# qec_pcb_v2.net
KiCad netlist of a schematic drawn in EAGLE
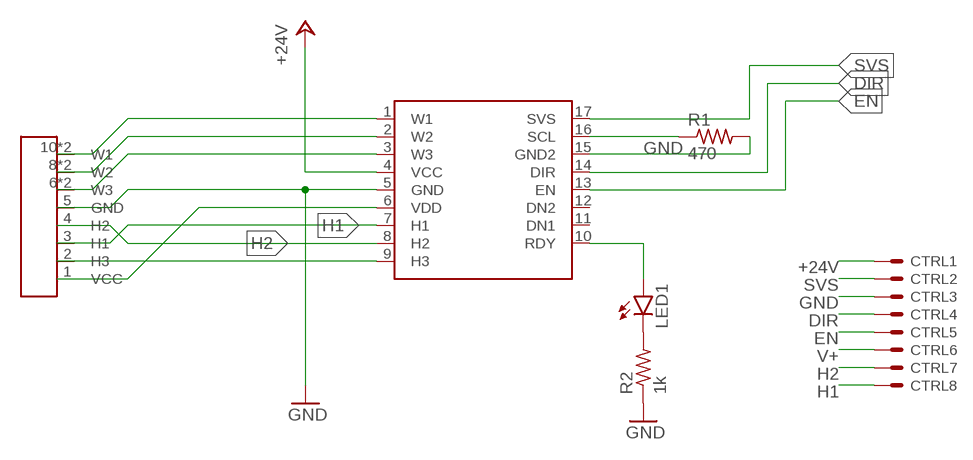
[diagram p0: schematic, sheet 1]

(export (version "E")
  (design (tool "Eeschema 10.0.6"))
  (components
    (comp (ref "CTRL")
      (value "JST8")
      (footprint "eagle-import:JST")
      (libsource (lib "eagle-import") (part "JST8"))
    )
    (comp (ref "K1")
      (value "68611114122")
      (footprint "eagle-import:68611114122")
      (libsource (lib "eagle-import") (part "68611114122"))
    )
    (comp (ref "LED1")
      (value "LEDCHIPLED_0805")
      (footprint "eagle-import:CHIPLED_0805")
      (libsource (lib "eagle-import") (part "LEDCHIPLED_0805"))
    )
    (comp (ref "R1")
      (value "470")
      (footprint "eagle-import:M0805")
      (libsource (lib "eagle-import") (part "R-US_M0805"))
    )
    (comp (ref "R2")
      (value "1k")
      (footprint "eagle-import:M0805")
      (libsource (lib "eagle-import") (part "R-US_M0805"))
    )
    (comp (ref "U$1")
      (value "1-Q-EC1-Q-EC-SMD")
      (footprint "eagle-import:1-Q-EC-SMD")
      (libsource (lib "eagle-import") (part "1-Q-EC1-Q-EC-SMD"))
    )
  )
  (nets
    (net (code "1") (name "+24V") (class "Default")
      (node (ref "CTRL") (pin "1") (pinfunction "S_1") (pintype "passive"))
      (node (ref "U$1") (pin "4") (pinfunction "VCC_4") (pintype "bidirectional"))
    )
    (net (code "2") (name "/V+") (class "Default")
      (node (ref "CTRL") (pin "6") (pinfunction "S_6") (pintype "passive"))
      (node (ref "K1") (pin "1") (pinfunction "VCC_1") (pintype "bidirectional"))
      (node (ref "U$1") (pin "6") (pinfunction "VDD_6") (pintype "bidirectional"))
    )
    (net (code "3") (name "DIR") (class "Default")
      (node (ref "CTRL") (pin "4") (pinfunction "S_4") (pintype "passive"))
      (node (ref "U$1") (pin "14") (pinfunction "DIR_14") (pintype "bidirectional"))
    )
    (net (code "4") (name "EN") (class "Default")
      (node (ref "CTRL") (pin "5") (pinfunction "S_5") (pintype "passive"))
      (node (ref "U$1") (pin "13") (pinfunction "EN_13") (pintype "bidirectional"))
    )
    (net (code "5") (name "GND") (class "Default")
      (node (ref "CTRL") (pin "3") (pinfunction "S_3") (pintype "passive"))
      (node (ref "K1") (pin "5") (pinfunction "GND_5") (pintype "bidirectional"))
      (node (ref "R1") (pin "2") (pinfunction "2_2") (pintype "passive"))
      (node (ref "R2") (pin "1") (pinfunction "1_1") (pintype "passive"))
      (node (ref "U$1") (pin "15") (pinfunction "GND2_15") (pintype "bidirectional"))
      (node (ref "U$1") (pin "5") (pinfunction "GND_5") (pintype "bidirectional"))
    )
    (net (code "6") (name "H1") (class "Default")
      (node (ref "CTRL") (pin "8") (pinfunction "S_8") (pintype "passive"))
      (node (ref "K1") (pin "3") (pinfunction "H1_3") (pintype "bidirectional"))
      (node (ref "U$1") (pin "7") (pinfunction "H1_7") (pintype "bidirectional"))
    )
    (net (code "7") (name "H2") (class "Default")
      (node (ref "CTRL") (pin "7") (pinfunction "S_7") (pintype "passive"))
      (node (ref "K1") (pin "4") (pinfunction "H2_4") (pintype "bidirectional"))
      (node (ref "U$1") (pin "8") (pinfunction "H2_8") (pintype "bidirectional"))
    )
    (net (code "8") (name "Net-(K1-H3)") (class "Default")
      (node (ref "K1") (pin "2") (pinfunction "H3_2") (pintype "bidirectional"))
      (node (ref "U$1") (pin "9") (pinfunction "H3_9") (pintype "bidirectional"))
    )
    (net (code "9") (name "Net-(LED1-PadC)") (class "Default")
      (node (ref "LED1") (pin "C") (pinfunction "C_C") (pintype "passive"))
      (node (ref "R2") (pin "2") (pinfunction "2_2") (pintype "passive"))
    )
    (net (code "10") (name "Net-(U$1-RDY)") (class "Default")
      (node (ref "LED1") (pin "A") (pinfunction "A_A") (pintype "passive"))
      (node (ref "U$1") (pin "10") (pinfunction "RDY_10") (pintype "bidirectional"))
    )
    (net (code "11") (name "Net-(U$1-SCL)") (class "Default")
      (node (ref "R1") (pin "1") (pinfunction "1_1") (pintype "passive"))
      (node (ref "U$1") (pin "16") (pinfunction "SCL_16") (pintype "bidirectional"))
    )
    (net (code "12") (name "Net-(U$1-W1)") (class "Default")
      (node (ref "K1") (pin "10") (pinfunction "W1_10") (pintype "bidirectional"))
      (node (ref "K1") (pin "11") (pinfunction "W1_11") (pintype "bidirectional"))
      (node (ref "U$1") (pin "1") (pinfunction "W1_1") (pintype "bidirectional"))
    )
    (net (code "13") (name "Net-(U$1-W2)") (class "Default")
      (node (ref "K1") (pin "8") (pinfunction "W2_8") (pintype "bidirectional"))
      (node (ref "K1") (pin "9") (pinfunction "W2_9") (pintype "bidirectional"))
      (node (ref "U$1") (pin "2") (pinfunction "W2_2") (pintype "bidirectional"))
    )
    (net (code "14") (name "Net-(U$1-W3)") (class "Default")
      (node (ref "K1") (pin "6") (pinfunction "W3_6") (pintype "bidirectional"))
      (node (ref "K1") (pin "7") (pinfunction "W3_7") (pintype "bidirectional"))
      (node (ref "U$1") (pin "3") (pinfunction "W3_3") (pintype "bidirectional"))
    )
    (net (code "15") (name "SVS") (class "Default")
      (node (ref "CTRL") (pin "2") (pinfunction "S_2") (pintype "passive"))
      (node (ref "U$1") (pin "17") (pinfunction "SVS_17") (pintype "bidirectional"))
    )
    (net (code "16") (name "unconnected-(U$1-DN1-Pad11)") (class "Default")
      (node (ref "U$1") (pin "11") (pinfunction "DN1_11") (pintype "bidirectional"))
    )
    (net (code "17") (name "unconnected-(U$1-DN2-Pad12)") (class "Default")
      (node (ref "U$1") (pin "12") (pinfunction "DN2_12") (pintype "bidirectional"))
    )
  )
)
